# motherboard.net
KiCad netlist of a schematic drawn in EAGLE
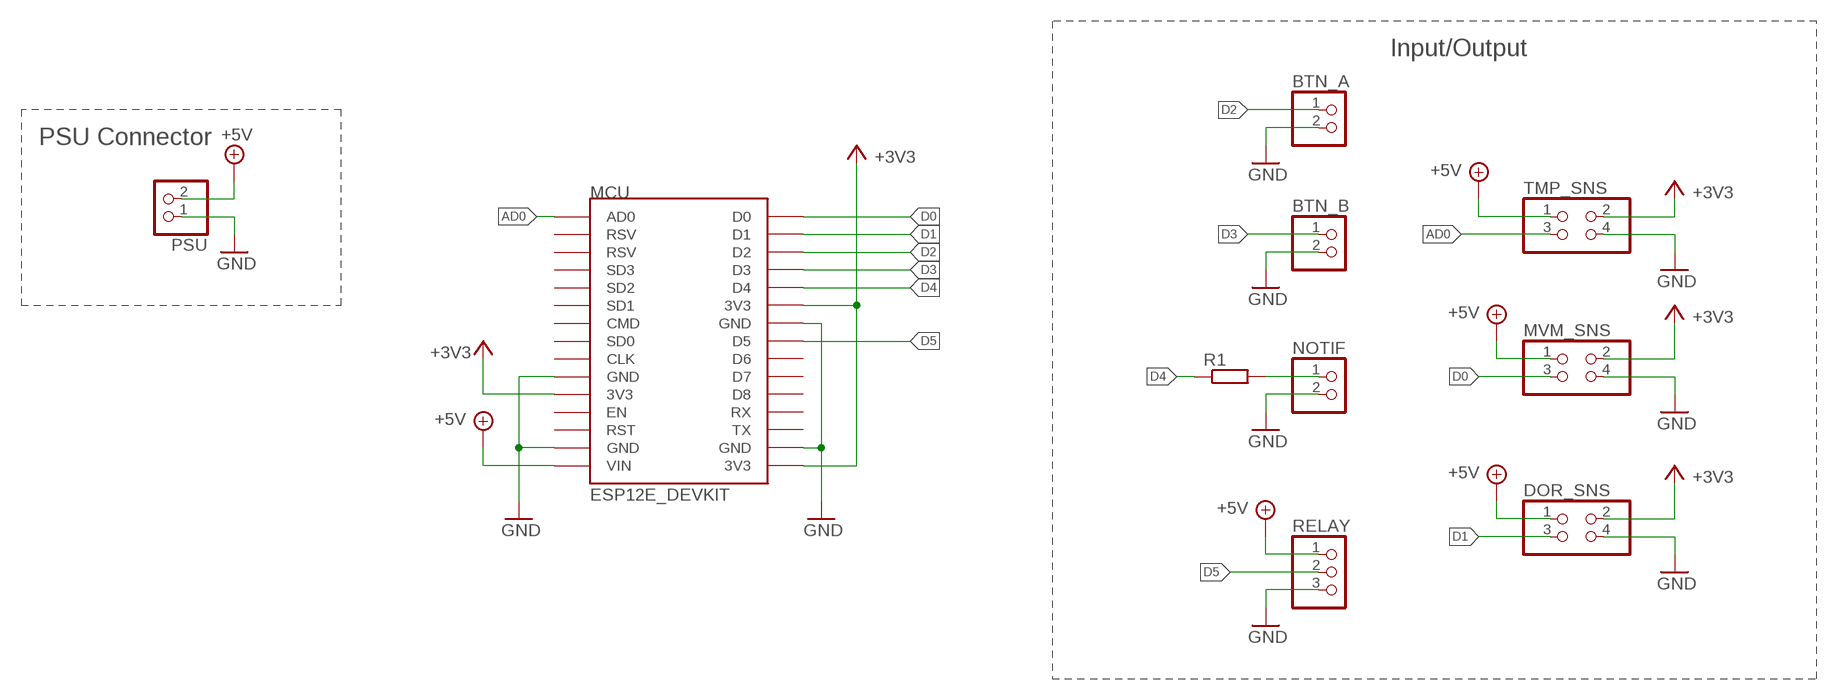
[diagram p0: schematic, sheet 1]

(export (version "E")
  (design (tool "Eeschema 10.0.6"))
  (components
    (comp (ref "BTN_A")
      (value "PINHD-1X2")
      (footprint "eagle-import:1X02")
      (libsource (lib "eagle-import") (part "PINHD-1X2"))
    )
    (comp (ref "BTN_B")
      (value "PINHD-1X2")
      (footprint "eagle-import:1X02")
      (libsource (lib "eagle-import") (part "PINHD-1X2"))
    )
    (comp (ref "DOR_SNS")
      (value "PINHD-2X2")
      (footprint "eagle-import:2X02")
      (libsource (lib "eagle-import") (part "PINHD-2X2"))
    )
    (comp (ref "MCU")
      (value "ESP12E_DEVKIT")
      (footprint "eagle-import:ESP12E_DEVKIT")
      (libsource (lib "eagle-import") (part "ESP12E_DEVKIT"))
    )
    (comp (ref "MVM_SNS")
      (value "PINHD-2X2")
      (footprint "eagle-import:2X02")
      (libsource (lib "eagle-import") (part "PINHD-2X2"))
    )
    (comp (ref "NOTIF")
      (value "PINHD-1X2")
      (footprint "eagle-import:1X02")
      (libsource (lib "eagle-import") (part "PINHD-1X2"))
    )
    (comp (ref "PSU")
      (value "PINHD-1X2")
      (footprint "eagle-import:1X02")
      (libsource (lib "eagle-import") (part "PINHD-1X2"))
    )
    (comp (ref "R1")
      (value "R-EU_0204/7")
      (footprint "eagle-import:0204_7")
      (libsource (lib "eagle-import") (part "R-EU_0204/7"))
    )
    (comp (ref "RELAY")
      (value "PINHD-1X3")
      (footprint "eagle-import:1X03")
      (libsource (lib "eagle-import") (part "PINHD-1X3"))
    )
    (comp (ref "TMP_SNS")
      (value "PINHD-2X2")
      (footprint "eagle-import:2X02")
      (libsource (lib "eagle-import") (part "PINHD-2X2"))
    )
  )
  (nets
    (net (code "1") (name "+3V3") (class "Default")
      (node (ref "DOR_SNS") (pin "2") (pinfunction "2_2") (pintype "passive"))
      (node (ref "MCU") (pin "3V3@0") (pinfunction "3V3_3V3@0") (pintype "bidirectional"))
      (node (ref "MCU") (pin "3V3@1") (pinfunction "3V3_3V3@1") (pintype "bidirectional"))
      (node (ref "MCU") (pin "3V3@2") (pinfunction "3V3_3V3@2") (pintype "bidirectional"))
      (node (ref "MVM_SNS") (pin "2") (pinfunction "2_2") (pintype "passive"))
      (node (ref "TMP_SNS") (pin "2") (pinfunction "2_2") (pintype "passive"))
    )
    (net (code "2") (name "+5V") (class "Default")
      (node (ref "DOR_SNS") (pin "1") (pinfunction "1_1") (pintype "passive"))
      (node (ref "MCU") (pin "VIN") (pinfunction "VIN_VIN") (pintype "bidirectional"))
      (node (ref "MVM_SNS") (pin "1") (pinfunction "1_1") (pintype "passive"))
      (node (ref "PSU") (pin "2") (pinfunction "2_2") (pintype "passive"))
      (node (ref "RELAY") (pin "1") (pinfunction "1_1") (pintype "passive"))
      (node (ref "TMP_SNS") (pin "1") (pinfunction "1_1") (pintype "passive"))
    )
    (net (code "3") (name "AD0") (class "Default")
      (node (ref "MCU") (pin "AD0") (pinfunction "AD0_AD0") (pintype "bidirectional"))
      (node (ref "TMP_SNS") (pin "3") (pinfunction "3_3") (pintype "passive"))
    )
    (net (code "4") (name "D0") (class "Default")
      (node (ref "MCU") (pin "D0") (pinfunction "D0_D0") (pintype "bidirectional"))
      (node (ref "MVM_SNS") (pin "3") (pinfunction "3_3") (pintype "passive"))
    )
    (net (code "5") (name "D1") (class "Default")
      (node (ref "DOR_SNS") (pin "3") (pinfunction "3_3") (pintype "passive"))
      (node (ref "MCU") (pin "D1") (pinfunction "D1_D1") (pintype "bidirectional"))
    )
    (net (code "6") (name "D2") (class "Default")
      (node (ref "BTN_A") (pin "1") (pinfunction "1_1") (pintype "passive"))
      (node (ref "MCU") (pin "D2") (pinfunction "D2_D2") (pintype "bidirectional"))
    )
    (net (code "7") (name "D3") (class "Default")
      (node (ref "BTN_B") (pin "1") (pinfunction "1_1") (pintype "passive"))
      (node (ref "MCU") (pin "D3") (pinfunction "D3_D3") (pintype "bidirectional"))
    )
    (net (code "8") (name "D4") (class "Default")
      (node (ref "MCU") (pin "D4") (pinfunction "D4_D4") (pintype "bidirectional"))
      (node (ref "R1") (pin "1") (pinfunction "1_1") (pintype "passive"))
    )
    (net (code "9") (name "D5") (class "Default")
      (node (ref "MCU") (pin "D5") (pinfunction "D5_D5") (pintype "bidirectional"))
      (node (ref "RELAY") (pin "2") (pinfunction "2_2") (pintype "passive"))
    )
    (net (code "10") (name "GND") (class "Default")
      (node (ref "BTN_A") (pin "2") (pinfunction "2_2") (pintype "passive"))
      (node (ref "BTN_B") (pin "2") (pinfunction "2_2") (pintype "passive"))
      (node (ref "DOR_SNS") (pin "4") (pinfunction "4_4") (pintype "passive"))
      (node (ref "MCU") (pin "GND@0") (pinfunction "GND_GND@0") (pintype "bidirectional"))
      (node (ref "MCU") (pin "GND@1") (pinfunction "GND_GND@1") (pintype "bidirectional"))
      (node (ref "MCU") (pin "GND@2") (pinfunction "GND_GND@2") (pintype "bidirectional"))
      (node (ref "MCU") (pin "GND@3") (pinfunction "GND_GND@3") (pintype "bidirectional"))
      (node (ref "MVM_SNS") (pin "4") (pinfunction "4_4") (pintype "passive"))
      (node (ref "NOTIF") (pin "2") (pinfunction "2_2") (pintype "passive"))
      (node (ref "PSU") (pin "1") (pinfunction "1_1") (pintype "passive"))
      (node (ref "RELAY") (pin "3") (pinfunction "3_3") (pintype "passive"))
      (node (ref "TMP_SNS") (pin "4") (pinfunction "4_4") (pintype "passive"))
    )
    (net (code "11") (name "Net-(NOTIF-Pad1)") (class "Default")
      (node (ref "NOTIF") (pin "1") (pinfunction "1_1") (pintype "passive"))
      (node (ref "R1") (pin "2") (pinfunction "2_2") (pintype "passive"))
    )
    (net (code "12") (name "unconnected-(MCU-PadCLK)") (class "Default")
      (node (ref "MCU") (pin "CLK") (pinfunction "CLK_CLK") (pintype "bidirectional"))
    )
    (net (code "13") (name "unconnected-(MCU-PadCMD)") (class "Default")
      (node (ref "MCU") (pin "CMD") (pinfunction "CMD_CMD") (pintype "bidirectional"))
    )
    (net (code "14") (name "unconnected-(MCU-PadD6)") (class "Default")
      (node (ref "MCU") (pin "D6") (pinfunction "D6_D6") (pintype "bidirectional"))
    )
    (net (code "15") (name "unconnected-(MCU-PadD7)") (class "Default")
      (node (ref "MCU") (pin "D7") (pinfunction "D7_D7") (pintype "bidirectional"))
    )
    (net (code "16") (name "unconnected-(MCU-PadD8)") (class "Default")
      (node (ref "MCU") (pin "D8") (pinfunction "D8_D8") (pintype "bidirectional"))
    )
    (net (code "17") (name "unconnected-(MCU-PadEN)") (class "Default")
      (node (ref "MCU") (pin "EN") (pinfunction "EN_EN") (pintype "bidirectional"))
    )
    (net (code "18") (name "unconnected-(MCU-PadRST)") (class "Default")
      (node (ref "MCU") (pin "RST") (pinfunction "RST_RST") (pintype "bidirectional"))
    )
    (net (code "19") (name "unconnected-(MCU-PadRX)") (class "Default")
      (node (ref "MCU") (pin "RX") (pinfunction "RX_RX") (pintype "bidirectional"))
    )
    (net (code "20") (name "unconnected-(MCU-PadSD0)") (class "Default")
      (node (ref "MCU") (pin "SD0") (pinfunction "SD0_SD0") (pintype "bidirectional"))
    )
    (net (code "21") (name "unconnected-(MCU-PadSD1)") (class "Default")
      (node (ref "MCU") (pin "SD1") (pinfunction "SD1_SD1") (pintype "bidirectional"))
    )
    (net (code "22") (name "unconnected-(MCU-PadSD2)") (class "Default")
      (node (ref "MCU") (pin "SD2") (pinfunction "SD2_SD2") (pintype "bidirectional"))
    )
    (net (code "23") (name "unconnected-(MCU-PadSD3)") (class "Default")
      (node (ref "MCU") (pin "SD3") (pinfunction "SD3_SD3") (pintype "bidirectional"))
    )
    (net (code "24") (name "unconnected-(MCU-PadTX)") (class "Default")
      (node (ref "MCU") (pin "TX") (pinfunction "TX_TX") (pintype "bidirectional"))
    )
    (net (code "25") (name "unconnected-(MCU-RSV-PadRSV@0)") (class "Default")
      (node (ref "MCU") (pin "RSV@0") (pinfunction "RSV_RSV@0") (pintype "bidirectional"))
    )
    (net (code "26") (name "unconnected-(MCU-RSV-PadRSV@1)") (class "Default")
      (node (ref "MCU") (pin "RSV@1") (pinfunction "RSV_RSV@1") (pintype "bidirectional"))
    )
  )
)
